# TriggerBoard_v3.net
KiCad netlist of a schematic drawn in EAGLE
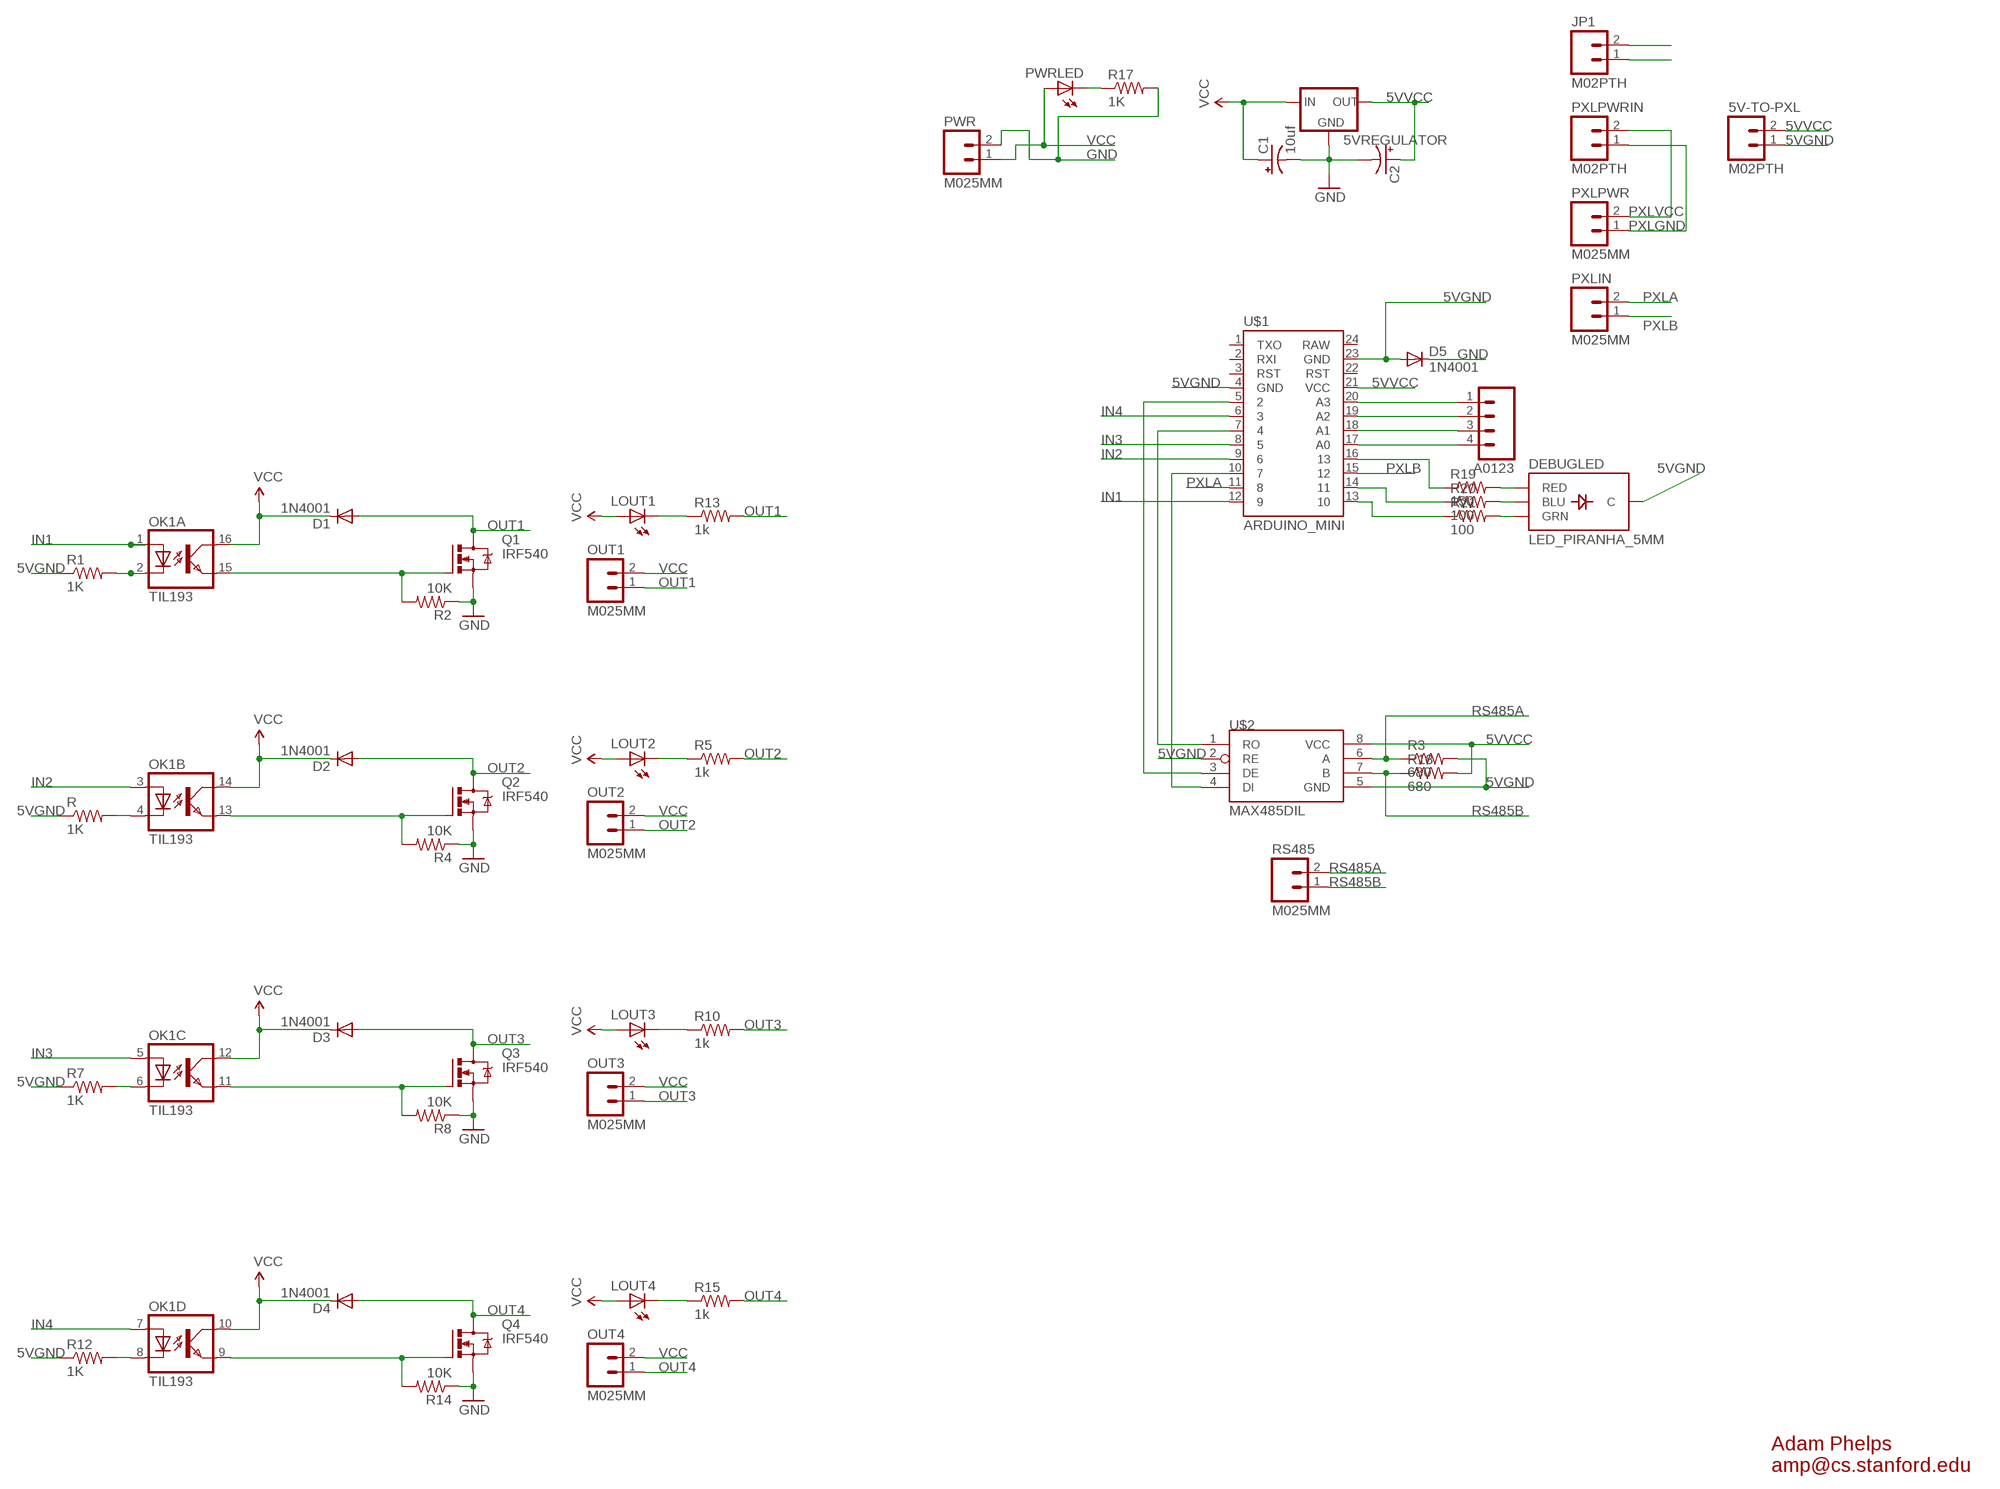
[diagram p0: schematic, sheet 1]

(export (version "E")
  (design (tool "Eeschema 10.0.6"))
  (components
    (comp (ref "5V-TO-PXL")
      (value "M02PTH")
      (footprint "eagle-import:1X02")
      (libsource (lib "eagle-import") (part "M02PTH"))
    )
    (comp (ref "5VREGULATOR")
      (value "V_REG_78XXSINK")
      (footprint "eagle-import:TO220-IGO")
      (libsource (lib "eagle-import") (part "V_REG_78XXSINK"))
    )
    (comp (ref "A0123")
      (value "M04PTH")
      (footprint "eagle-import:1X04")
      (libsource (lib "eagle-import") (part "M04PTH"))
    )
    (comp (ref "C1")
      (value "10uf")
      (footprint "eagle-import:CPOL-RADIAL-10UF-25V")
      (libsource (lib "eagle-import") (part "CAP_POLPTH2"))
    )
    (comp (ref "C2")
      (value "CAP_POLPTH2")
      (footprint "eagle-import:CPOL-RADIAL-10UF-25V")
      (libsource (lib "eagle-import") (part "CAP_POLPTH2"))
    )
    (comp (ref "D1")
      (value "1N4001")
      (footprint "eagle-import:DIODE-1N4001")
      (libsource (lib "eagle-import") (part "DIODEPTH"))
    )
    (comp (ref "D2")
      (value "1N4001")
      (footprint "eagle-import:DIODE-1N4001")
      (libsource (lib "eagle-import") (part "DIODEPTH"))
    )
    (comp (ref "D3")
      (value "1N4001")
      (footprint "eagle-import:DIODE-1N4001")
      (libsource (lib "eagle-import") (part "DIODEPTH"))
    )
    (comp (ref "D4")
      (value "1N4001")
      (footprint "eagle-import:DIODE-1N4001")
      (libsource (lib "eagle-import") (part "DIODEPTH"))
    )
    (comp (ref "D5")
      (value "1N4001")
      (footprint "eagle-import:DIODE-1N4001-KIT")
      (libsource (lib "eagle-import") (part "DIODE"))
    )
    (comp (ref "DEBUGLED")
      (value "LED_PIRANHA_5MM")
      (footprint "eagle-import:LED_PIRANHA_5MM")
      (libsource (lib "eagle-import") (part "LED_PIRANHA_5MM"))
    )
    (comp (ref "JP1")
      (value "M02PTH")
      (footprint "eagle-import:1X02")
      (libsource (lib "eagle-import") (part "M02PTH"))
    )
    (comp (ref "LOUT1")
      (value "LED3MM")
      (footprint "eagle-import:LED3MM")
      (libsource (lib "eagle-import") (part "LED3MM"))
    )
    (comp (ref "LOUT2")
      (value "LED3MM")
      (footprint "eagle-import:LED3MM")
      (libsource (lib "eagle-import") (part "LED3MM"))
    )
    (comp (ref "LOUT3")
      (value "LED3MM")
      (footprint "eagle-import:LED3MM")
      (libsource (lib "eagle-import") (part "LED3MM"))
    )
    (comp (ref "LOUT4")
      (value "LED3MM")
      (footprint "eagle-import:LED3MM")
      (libsource (lib "eagle-import") (part "LED3MM"))
    )
    (comp (ref "OK1")
      (value "TIL193")
      (footprint "eagle-import:DIL16")
      (libsource (lib "eagle-import") (part "TIL193"))
    )
    (comp (ref "OUT1")
      (value "M025MM")
      (footprint "eagle-import:SCREWTERMINAL-5MM-2")
      (libsource (lib "eagle-import") (part "M025MM"))
    )
    (comp (ref "OUT2")
      (value "M025MM")
      (footprint "eagle-import:SCREWTERMINAL-5MM-2")
      (libsource (lib "eagle-import") (part "M025MM"))
    )
    (comp (ref "OUT3")
      (value "M025MM")
      (footprint "eagle-import:SCREWTERMINAL-5MM-2")
      (libsource (lib "eagle-import") (part "M025MM"))
    )
    (comp (ref "OUT4")
      (value "M025MM")
      (footprint "eagle-import:SCREWTERMINAL-5MM-2")
      (libsource (lib "eagle-import") (part "M025MM"))
    )
    (comp (ref "PWR")
      (value "M025MM")
      (footprint "eagle-import:SCREWTERMINAL-5MM-2")
      (libsource (lib "eagle-import") (part "M025MM"))
    )
    (comp (ref "PWRLED")
      (value "LED5MM")
      (footprint "eagle-import:LED5MM")
      (libsource (lib "eagle-import") (part "LED5MM"))
    )
    (comp (ref "PXLIN")
      (value "M025MM")
      (footprint "eagle-import:SCREWTERMINAL-5MM-2")
      (libsource (lib "eagle-import") (part "M025MM"))
    )
    (comp (ref "PXLPWR")
      (value "M025MM")
      (footprint "eagle-import:SCREWTERMINAL-5MM-2")
      (libsource (lib "eagle-import") (part "M025MM"))
    )
    (comp (ref "PXLPWRIN")
      (value "M02PTH")
      (footprint "eagle-import:1X02")
      (libsource (lib "eagle-import") (part "M02PTH"))
    )
    (comp (ref "Q1")
      (value "IRF540")
      (footprint "eagle-import:TO220BV")
      (libsource (lib "eagle-import") (part "IRF540"))
    )
    (comp (ref "Q2")
      (value "IRF540")
      (footprint "eagle-import:TO220BV")
      (libsource (lib "eagle-import") (part "IRF540"))
    )
    (comp (ref "Q3")
      (value "IRF540")
      (footprint "eagle-import:TO220BV")
      (libsource (lib "eagle-import") (part "IRF540"))
    )
    (comp (ref "Q4")
      (value "IRF540")
      (footprint "eagle-import:TO220BV")
      (libsource (lib "eagle-import") (part "IRF540"))
    )
    (comp (ref "R")
      (value "1K")
      (footprint "eagle-import:AXIAL-0.4")
      (libsource (lib "eagle-import") (part "RESISTORPTH-1/4W"))
    )
    (comp (ref "R1")
      (value "1K")
      (footprint "eagle-import:AXIAL-0.4")
      (libsource (lib "eagle-import") (part "RESISTORPTH-1/4W"))
    )
    (comp (ref "R2")
      (value "10K")
      (footprint "eagle-import:AXIAL-0.4")
      (libsource (lib "eagle-import") (part "RESISTORPTH-1/4W"))
    )
    (comp (ref "R3")
      (value "680")
      (footprint "eagle-import:AXIAL-0.4")
      (libsource (lib "eagle-import") (part "RESISTORPTH-1/4W"))
    )
    (comp (ref "R4")
      (value "10K")
      (footprint "eagle-import:AXIAL-0.4")
      (libsource (lib "eagle-import") (part "RESISTORPTH-1/4W"))
    )
    (comp (ref "R5")
      (value "1k")
      (footprint "eagle-import:AXIAL-0.4")
      (libsource (lib "eagle-import") (part "RESISTORPTH-1/4W"))
    )
    (comp (ref "R7")
      (value "1K")
      (footprint "eagle-import:AXIAL-0.4")
      (libsource (lib "eagle-import") (part "RESISTORPTH-1/4W"))
    )
    (comp (ref "R8")
      (value "10K")
      (footprint "eagle-import:AXIAL-0.4")
      (libsource (lib "eagle-import") (part "RESISTORPTH-1/4W"))
    )
    (comp (ref "R10")
      (value "1k")
      (footprint "eagle-import:AXIAL-0.4")
      (libsource (lib "eagle-import") (part "RESISTORPTH-1/4W"))
    )
    (comp (ref "R12")
      (value "1K")
      (footprint "eagle-import:AXIAL-0.4")
      (libsource (lib "eagle-import") (part "RESISTORPTH-1/4W"))
    )
    (comp (ref "R13")
      (value "1k")
      (footprint "eagle-import:AXIAL-0.4")
      (libsource (lib "eagle-import") (part "RESISTORPTH-1/4W"))
    )
    (comp (ref "R14")
      (value "10K")
      (footprint "eagle-import:AXIAL-0.4")
      (libsource (lib "eagle-import") (part "RESISTORPTH-1/4W"))
    )
    (comp (ref "R15")
      (value "1k")
      (footprint "eagle-import:AXIAL-0.4")
      (libsource (lib "eagle-import") (part "RESISTORPTH-1/4W"))
    )
    (comp (ref "R17")
      (value "1K")
      (footprint "eagle-import:AXIAL-0.4")
      (libsource (lib "eagle-import") (part "RESISTORPTH-1/4W"))
    )
    (comp (ref "R18")
      (value "680")
      (footprint "eagle-import:AXIAL-0.4")
      (libsource (lib "eagle-import") (part "RESISTORPTH-1/4W"))
    )
    (comp (ref "R19")
      (value "150")
      (footprint "eagle-import:AXIAL-0.4")
      (libsource (lib "eagle-import") (part "RESISTORPTH-1/4W"))
    )
    (comp (ref "R20")
      (value "100")
      (footprint "eagle-import:AXIAL-0.4")
      (libsource (lib "eagle-import") (part "RESISTORPTH-1/4W"))
    )
    (comp (ref "R21")
      (value "100")
      (footprint "eagle-import:AXIAL-0.4")
      (libsource (lib "eagle-import") (part "RESISTORPTH-1/4W"))
    )
    (comp (ref "RS485")
      (value "M025MM")
      (footprint "eagle-import:SCREWTERMINAL-5MM-2")
      (libsource (lib "eagle-import") (part "M025MM"))
    )
    (comp (ref "U$1")
      (value "ARDUINO_MINI")
      (footprint "eagle-import:ARDUINO_MINI")
      (libsource (lib "eagle-import") (part "ARDUINO_MINI"))
    )
    (comp (ref "U$2")
      (value "MAX485DIL")
      (footprint "eagle-import:DIL08")
      (libsource (lib "eagle-import") (part "MAX485DIL"))
    )
  )
  (nets
    (net (code "1") (name "/5VGND") (class "Default")
      (node (ref "5V-TO-PXL") (pin "1") (pinfunction "1_1") (pintype "passive"))
      (node (ref "D5") (pin "A") (pinfunction "A_A") (pintype "passive"))
      (node (ref "DEBUGLED") (pin "-") (pinfunction "C_-") (pintype "bidirectional"))
      (node (ref "R") (pin "P$1") (pinfunction "1_P$1") (pintype "passive"))
      (node (ref "R1") (pin "P$1") (pinfunction "1_P$1") (pintype "passive"))
      (node (ref "R12") (pin "P$1") (pinfunction "1_P$1") (pintype "passive"))
      (node (ref "R3") (pin "P$2") (pinfunction "2_P$2") (pintype "passive"))
      (node (ref "R7") (pin "P$1") (pinfunction "1_P$1") (pintype "passive"))
      (node (ref "U$1") (pin "23") (pinfunction "GND_23") (pintype "bidirectional"))
      (node (ref "U$1") (pin "4") (pinfunction "GND_4") (pintype "bidirectional"))
      (node (ref "U$2") (pin "2") (pinfunction "RE_2") (pintype "bidirectional"))
      (node (ref "U$2") (pin "5") (pinfunction "GND_5") (pintype "bidirectional"))
    )
    (net (code "2") (name "/5VVCC") (class "Default")
      (node (ref "5V-TO-PXL") (pin "2") (pinfunction "2_2") (pintype "passive"))
      (node (ref "5VREGULATOR") (pin "OUT") (pinfunction "OUT_OUT") (pintype "output"))
      (node (ref "C2") (pin "1") (pinfunction "+_1") (pintype "passive"))
      (node (ref "R18") (pin "P$2") (pinfunction "2_P$2") (pintype "passive"))
      (node (ref "U$1") (pin "21") (pinfunction "VCC_21") (pintype "bidirectional"))
      (node (ref "U$2") (pin "8") (pinfunction "VCC_8") (pintype "bidirectional"))
    )
    (net (code "3") (name "/IN1") (class "Default")
      (node (ref "OK1") (pin "1") (pinfunction "A_1") (pintype "passive"))
      (node (ref "U$1") (pin "12") (pinfunction "9_12") (pintype "bidirectional"))
    )
    (net (code "4") (name "/IN2") (class "Default")
      (node (ref "OK1") (pin "3") (pinfunction "A_3") (pintype "passive"))
      (node (ref "U$1") (pin "9") (pinfunction "6_9") (pintype "bidirectional"))
    )
    (net (code "5") (name "/IN3") (class "Default")
      (node (ref "OK1") (pin "5") (pinfunction "A_5") (pintype "passive"))
      (node (ref "U$1") (pin "8") (pinfunction "5_8") (pintype "bidirectional"))
    )
    (net (code "6") (name "/IN4") (class "Default")
      (node (ref "OK1") (pin "7") (pinfunction "A_7") (pintype "passive"))
      (node (ref "U$1") (pin "6") (pinfunction "3_6") (pintype "bidirectional"))
    )
    (net (code "7") (name "/OUT1") (class "Default")
      (node (ref "D1") (pin "A") (pinfunction "A_A") (pintype "passive"))
      (node (ref "OUT1") (pin "1") (pinfunction "1_1") (pintype "passive"))
      (node (ref "Q1") (pin "D") (pinfunction "D_D") (pintype "passive"))
      (node (ref "R13") (pin "P$2") (pinfunction "2_P$2") (pintype "passive"))
    )
    (net (code "8") (name "/OUT2") (class "Default")
      (node (ref "D2") (pin "A") (pinfunction "A_A") (pintype "passive"))
      (node (ref "OUT2") (pin "1") (pinfunction "1_1") (pintype "passive"))
      (node (ref "Q2") (pin "D") (pinfunction "D_D") (pintype "passive"))
      (node (ref "R5") (pin "P$2") (pinfunction "2_P$2") (pintype "passive"))
    )
    (net (code "9") (name "/OUT3") (class "Default")
      (node (ref "D3") (pin "A") (pinfunction "A_A") (pintype "passive"))
      (node (ref "OUT3") (pin "1") (pinfunction "1_1") (pintype "passive"))
      (node (ref "Q3") (pin "D") (pinfunction "D_D") (pintype "passive"))
      (node (ref "R10") (pin "P$2") (pinfunction "2_P$2") (pintype "passive"))
    )
    (net (code "10") (name "/OUT4") (class "Default")
      (node (ref "D4") (pin "A") (pinfunction "A_A") (pintype "passive"))
      (node (ref "OUT4") (pin "1") (pinfunction "1_1") (pintype "passive"))
      (node (ref "Q4") (pin "D") (pinfunction "D_D") (pintype "passive"))
      (node (ref "R15") (pin "P$2") (pinfunction "2_P$2") (pintype "passive"))
    )
    (net (code "11") (name "/PXLA") (class "Default")
      (node (ref "PXLIN") (pin "2") (pinfunction "2_2") (pintype "passive"))
      (node (ref "U$1") (pin "11") (pinfunction "8_11") (pintype "bidirectional"))
    )
    (net (code "12") (name "/PXLB") (class "Default")
      (node (ref "PXLIN") (pin "1") (pinfunction "1_1") (pintype "passive"))
      (node (ref "U$1") (pin "15") (pinfunction "12_15") (pintype "bidirectional"))
    )
    (net (code "13") (name "/PXLGND") (class "Default")
      (node (ref "PXLPWR") (pin "1") (pinfunction "1_1") (pintype "passive"))
      (node (ref "PXLPWRIN") (pin "1") (pinfunction "1_1") (pintype "passive"))
    )
    (net (code "14") (name "/PXLVCC") (class "Default")
      (node (ref "PXLPWR") (pin "2") (pinfunction "2_2") (pintype "passive"))
      (node (ref "PXLPWRIN") (pin "2") (pinfunction "2_2") (pintype "passive"))
    )
    (net (code "15") (name "/RS485A") (class "Default")
      (node (ref "R3") (pin "P$1") (pinfunction "1_P$1") (pintype "passive"))
      (node (ref "RS485") (pin "2") (pinfunction "2_2") (pintype "passive"))
      (node (ref "U$2") (pin "6") (pinfunction "A_6") (pintype "bidirectional"))
    )
    (net (code "16") (name "/RS485B") (class "Default")
      (node (ref "R18") (pin "P$1") (pinfunction "1_P$1") (pintype "passive"))
      (node (ref "RS485") (pin "1") (pinfunction "1_1") (pintype "passive"))
      (node (ref "U$2") (pin "7") (pinfunction "B_7") (pintype "bidirectional"))
    )
    (net (code "17") (name "GND") (class "Default")
      (node (ref "5VREGULATOR") (pin "GND") (pinfunction "GND_GND") (pintype "input"))
      (node (ref "C1") (pin "2") (pinfunction "-_2") (pintype "passive"))
      (node (ref "C2") (pin "2") (pinfunction "-_2") (pintype "passive"))
      (node (ref "D5") (pin "C") (pinfunction "C_C") (pintype "passive"))
      (node (ref "JP1") (pin "1") (pinfunction "1_1") (pintype "passive"))
      (node (ref "PWR") (pin "2") (pinfunction "2_2") (pintype "passive"))
      (node (ref "Q1") (pin "S") (pinfunction "S_S") (pintype "passive"))
      (node (ref "Q2") (pin "S") (pinfunction "S_S") (pintype "passive"))
      (node (ref "Q3") (pin "S") (pinfunction "S_S") (pintype "passive"))
      (node (ref "Q4") (pin "S") (pinfunction "S_S") (pintype "passive"))
      (node (ref "R14") (pin "P$1") (pinfunction "1_P$1") (pintype "passive"))
      (node (ref "R17") (pin "P$2") (pinfunction "2_P$2") (pintype "passive"))
      (node (ref "R2") (pin "P$1") (pinfunction "1_P$1") (pintype "passive"))
      (node (ref "R4") (pin "P$1") (pinfunction "1_P$1") (pintype "passive"))
      (node (ref "R8") (pin "P$1") (pinfunction "1_P$1") (pintype "passive"))
    )
    (net (code "18") (name "Net-(DEBUGLED-BLU)") (class "Default")
      (node (ref "DEBUGLED") (pin "B") (pinfunction "BLU_B") (pintype "bidirectional"))
      (node (ref "R20") (pin "P$2") (pinfunction "2_P$2") (pintype "passive"))
    )
    (net (code "19") (name "Net-(DEBUGLED-GRN)") (class "Default")
      (node (ref "DEBUGLED") (pin "G") (pinfunction "GRN_G") (pintype "bidirectional"))
      (node (ref "R21") (pin "P$2") (pinfunction "2_P$2") (pintype "passive"))
    )
    (net (code "20") (name "Net-(DEBUGLED-RED)") (class "Default")
      (node (ref "DEBUGLED") (pin "R") (pinfunction "RED_R") (pintype "bidirectional"))
      (node (ref "R19") (pin "P$2") (pinfunction "2_P$2") (pintype "passive"))
    )
    (net (code "21") (name "Net-(LOUT1-C)") (class "Default")
      (node (ref "LOUT1") (pin "K") (pinfunction "C_K") (pintype "passive"))
      (node (ref "R13") (pin "P$1") (pinfunction "1_P$1") (pintype "passive"))
    )
    (net (code "22") (name "Net-(LOUT2-C)") (class "Default")
      (node (ref "LOUT2") (pin "K") (pinfunction "C_K") (pintype "passive"))
      (node (ref "R5") (pin "P$1") (pinfunction "1_P$1") (pintype "passive"))
    )
    (net (code "23") (name "Net-(LOUT3-C)") (class "Default")
      (node (ref "LOUT3") (pin "K") (pinfunction "C_K") (pintype "passive"))
      (node (ref "R10") (pin "P$1") (pinfunction "1_P$1") (pintype "passive"))
    )
    (net (code "24") (name "Net-(LOUT4-C)") (class "Default")
      (node (ref "LOUT4") (pin "K") (pinfunction "C_K") (pintype "passive"))
      (node (ref "R15") (pin "P$1") (pinfunction "1_P$1") (pintype "passive"))
    )
    (net (code "25") (name "Net-(OK1A-C)") (class "Default")
      (node (ref "OK1") (pin "2") (pinfunction "C_2") (pintype "passive"))
      (node (ref "R1") (pin "P$2") (pinfunction "2_P$2") (pintype "passive"))
    )
    (net (code "26") (name "Net-(OK1A-EMIT)") (class "Default")
      (node (ref "OK1") (pin "15") (pinfunction "EMIT_15") (pintype "passive"))
      (node (ref "Q1") (pin "G") (pinfunction "G_G") (pintype "passive"))
      (node (ref "R2") (pin "P$2") (pinfunction "2_P$2") (pintype "passive"))
    )
    (net (code "27") (name "Net-(OK1B-C)") (class "Default")
      (node (ref "OK1") (pin "4") (pinfunction "C_4") (pintype "passive"))
      (node (ref "R") (pin "P$2") (pinfunction "2_P$2") (pintype "passive"))
    )
    (net (code "28") (name "Net-(OK1B-EMIT)") (class "Default")
      (node (ref "OK1") (pin "13") (pinfunction "EMIT_13") (pintype "passive"))
      (node (ref "Q2") (pin "G") (pinfunction "G_G") (pintype "passive"))
      (node (ref "R4") (pin "P$2") (pinfunction "2_P$2") (pintype "passive"))
    )
    (net (code "29") (name "Net-(OK1C-C)") (class "Default")
      (node (ref "OK1") (pin "6") (pinfunction "C_6") (pintype "passive"))
      (node (ref "R7") (pin "P$2") (pinfunction "2_P$2") (pintype "passive"))
    )
    (net (code "30") (name "Net-(OK1C-EMIT)") (class "Default")
      (node (ref "OK1") (pin "11") (pinfunction "EMIT_11") (pintype "passive"))
      (node (ref "Q3") (pin "G") (pinfunction "G_G") (pintype "passive"))
      (node (ref "R8") (pin "P$2") (pinfunction "2_P$2") (pintype "passive"))
    )
    (net (code "31") (name "Net-(OK1D-C)") (class "Default")
      (node (ref "OK1") (pin "8") (pinfunction "C_8") (pintype "passive"))
      (node (ref "R12") (pin "P$2") (pinfunction "2_P$2") (pintype "passive"))
    )
    (net (code "32") (name "Net-(OK1D-EMIT)") (class "Default")
      (node (ref "OK1") (pin "9") (pinfunction "EMIT_9") (pintype "passive"))
      (node (ref "Q4") (pin "G") (pinfunction "G_G") (pintype "passive"))
      (node (ref "R14") (pin "P$2") (pinfunction "2_P$2") (pintype "passive"))
    )
    (net (code "33") (name "Net-(PWRLED-C)") (class "Default")
      (node (ref "PWRLED") (pin "K") (pinfunction "C_K") (pintype "passive"))
      (node (ref "R17") (pin "P$1") (pinfunction "1_P$1") (pintype "passive"))
    )
    (net (code "34") (name "Net-(R19-1)") (class "Default")
      (node (ref "R19") (pin "P$1") (pinfunction "1_P$1") (pintype "passive"))
      (node (ref "U$1") (pin "16") (pinfunction "13_16") (pintype "bidirectional"))
    )
    (net (code "35") (name "Net-(R20-1)") (class "Default")
      (node (ref "R20") (pin "P$1") (pinfunction "1_P$1") (pintype "passive"))
      (node (ref "U$1") (pin "14") (pinfunction "11_14") (pintype "bidirectional"))
    )
    (net (code "36") (name "Net-(R21-1)") (class "Default")
      (node (ref "R21") (pin "P$1") (pinfunction "1_P$1") (pintype "passive"))
      (node (ref "U$1") (pin "13") (pinfunction "10_13") (pintype "bidirectional"))
    )
    (net (code "37") (name "Net-(U$1-2)") (class "Default")
      (node (ref "U$1") (pin "5") (pinfunction "2_5") (pintype "bidirectional"))
      (node (ref "U$2") (pin "3") (pinfunction "DE_3") (pintype "bidirectional"))
    )
    (net (code "38") (name "Net-(U$1-4)") (class "Default")
      (node (ref "U$1") (pin "7") (pinfunction "4_7") (pintype "bidirectional"))
      (node (ref "U$2") (pin "1") (pinfunction "RO_1") (pintype "bidirectional"))
    )
    (net (code "39") (name "Net-(U$1-7)") (class "Default")
      (node (ref "U$1") (pin "10") (pinfunction "7_10") (pintype "bidirectional"))
      (node (ref "U$2") (pin "4") (pinfunction "DI_4") (pintype "bidirectional"))
    )
    (net (code "40") (name "Net-(U$1-A0)") (class "Default")
      (node (ref "A0123") (pin "4") (pinfunction "4_4") (pintype "passive"))
      (node (ref "U$1") (pin "17") (pinfunction "A0_17") (pintype "bidirectional"))
    )
    (net (code "41") (name "Net-(U$1-A1)") (class "Default")
      (node (ref "A0123") (pin "3") (pinfunction "3_3") (pintype "passive"))
      (node (ref "U$1") (pin "18") (pinfunction "A1_18") (pintype "bidirectional"))
    )
    (net (code "42") (name "Net-(U$1-A2)") (class "Default")
      (node (ref "A0123") (pin "2") (pinfunction "2_2") (pintype "passive"))
      (node (ref "U$1") (pin "19") (pinfunction "A2_19") (pintype "bidirectional"))
    )
    (net (code "43") (name "Net-(U$1-A3)") (class "Default")
      (node (ref "A0123") (pin "1") (pinfunction "1_1") (pintype "passive"))
      (node (ref "U$1") (pin "20") (pinfunction "A3_20") (pintype "bidirectional"))
    )
    (net (code "44") (name "VCC") (class "Default")
      (node (ref "5VREGULATOR") (pin "IN") (pinfunction "IN_IN") (pintype "input"))
      (node (ref "C1") (pin "1") (pinfunction "+_1") (pintype "passive"))
      (node (ref "D1") (pin "C") (pinfunction "C_C") (pintype "passive"))
      (node (ref "D2") (pin "C") (pinfunction "C_C") (pintype "passive"))
      (node (ref "D3") (pin "C") (pinfunction "C_C") (pintype "passive"))
      (node (ref "D4") (pin "C") (pinfunction "C_C") (pintype "passive"))
      (node (ref "JP1") (pin "2") (pinfunction "2_2") (pintype "passive"))
      (node (ref "LOUT1") (pin "A") (pinfunction "A_A") (pintype "passive"))
      (node (ref "LOUT2") (pin "A") (pinfunction "A_A") (pintype "passive"))
      (node (ref "LOUT3") (pin "A") (pinfunction "A_A") (pintype "passive"))
      (node (ref "LOUT4") (pin "A") (pinfunction "A_A") (pintype "passive"))
      (node (ref "OK1") (pin "10") (pinfunction "COL_10") (pintype "passive"))
      (node (ref "OK1") (pin "12") (pinfunction "COL_12") (pintype "passive"))
      (node (ref "OK1") (pin "14") (pinfunction "COL_14") (pintype "passive"))
      (node (ref "OK1") (pin "16") (pinfunction "COL_16") (pintype "passive"))
      (node (ref "OUT1") (pin "2") (pinfunction "2_2") (pintype "passive"))
      (node (ref "OUT2") (pin "2") (pinfunction "2_2") (pintype "passive"))
      (node (ref "OUT3") (pin "2") (pinfunction "2_2") (pintype "passive"))
      (node (ref "OUT4") (pin "2") (pinfunction "2_2") (pintype "passive"))
      (node (ref "PWR") (pin "1") (pinfunction "1_1") (pintype "passive"))
      (node (ref "PWRLED") (pin "A") (pinfunction "A_A") (pintype "passive"))
    )
    (net (code "45") (name "unconnected-(U$1-RAW-Pad24)") (class "Default")
      (node (ref "U$1") (pin "24") (pinfunction "RAW_24") (pintype "bidirectional"))
    )
    (net (code "46") (name "unconnected-(U$1-RST-Pad3)") (class "Default")
      (node (ref "U$1") (pin "3") (pinfunction "RST_3") (pintype "bidirectional"))
    )
    (net (code "47") (name "unconnected-(U$1-RST-Pad22)") (class "Default")
      (node (ref "U$1") (pin "22") (pinfunction "RST_22") (pintype "bidirectional"))
    )
    (net (code "48") (name "unconnected-(U$1-RXI-Pad2)") (class "Default")
      (node (ref "U$1") (pin "2") (pinfunction "RXI_2") (pintype "bidirectional"))
    )
    (net (code "49") (name "unconnected-(U$1-TXO-Pad1)") (class "Default")
      (node (ref "U$1") (pin "1") (pinfunction "TXO_1") (pintype "bidirectional"))
    )
  )
)
